# bottom_simp_power.net
KiCad netlist of a schematic drawn in Altium Designer
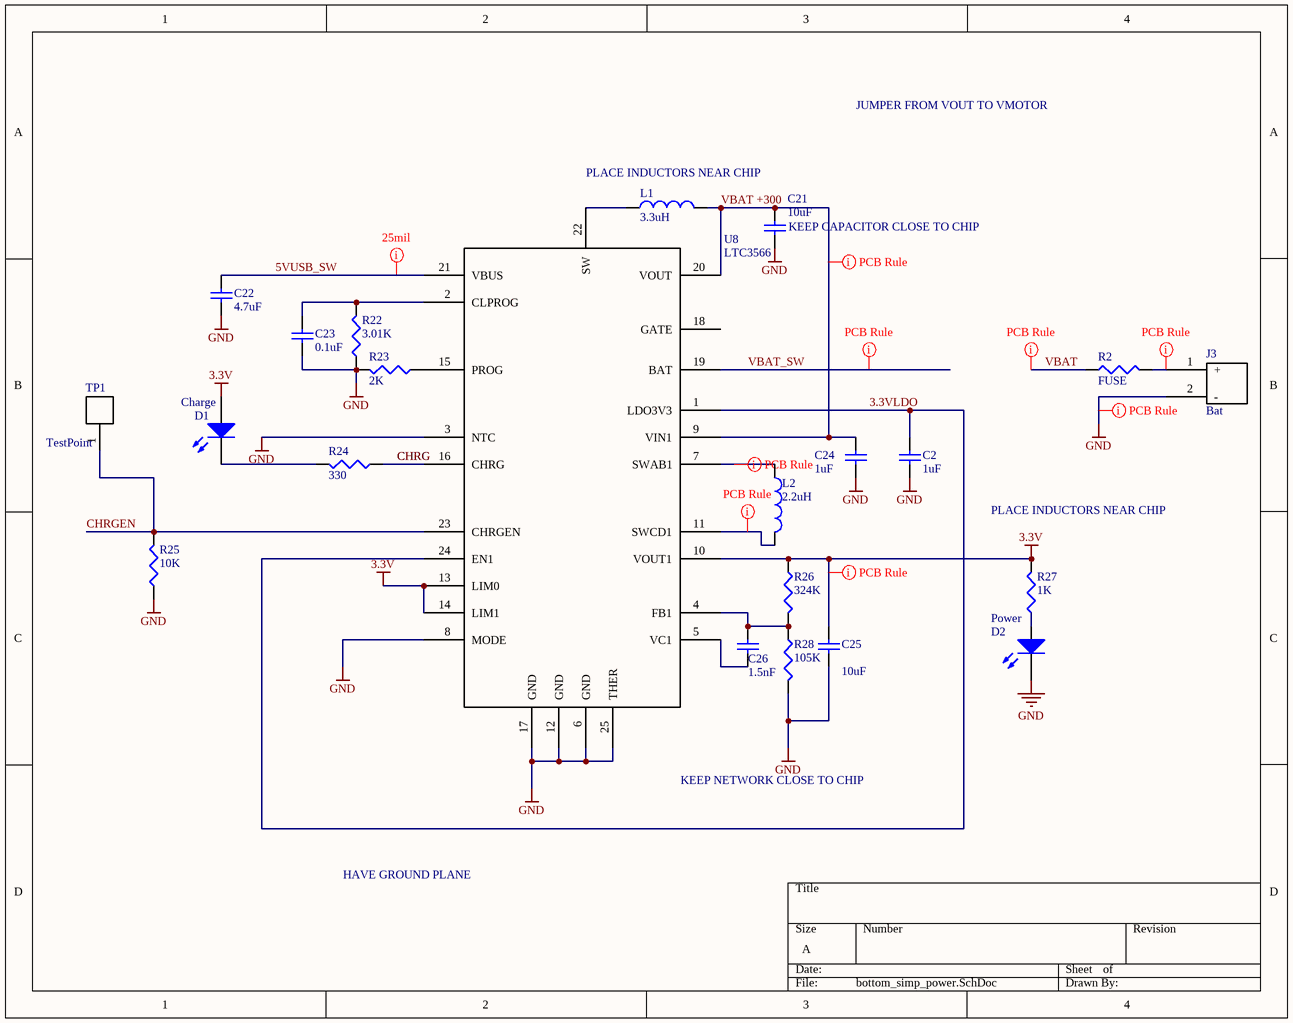
[diagram p0: bottom_simp_power.SchDoc]

(export (version "E")
  (design (tool "Eeschema 10.0.6"))
  (components
    (comp (ref "C2")
      (value "1uF")
      (footprint "CAPC1608L")
      (description "Capacitor")
      (fields (field (name "Comment") "Cap") (field (name "PUBLISHER") "Altium Limited"))
      (libsource (lib "Miscellaneous Devices") (part "Cap"))
    )
    (comp (ref "C21")
      (value "10uF")
      (footprint "CAPC1608L")
      (description "Capacitor")
      (fields (field (name "Comment") "Cap") (field (name "PUBLISHER") "Altium Limited"))
      (libsource (lib "Miscellaneous Devices") (part "Cap"))
    )
    (comp (ref "C22")
      (value "4.7uF")
      (footprint "CAPC1608L")
      (description "Capacitor")
      (fields (field (name "Comment") "Cap") (field (name "PUBLISHER") "Altium Limited"))
      (libsource (lib "Miscellaneous Devices") (part "Cap"))
    )
    (comp (ref "C23")
      (value "0.1uF")
      (footprint "CAPC1005L")
      (description "Capacitor")
      (fields (field (name "Comment") "Cap") (field (name "PUBLISHER") "Altium Limited"))
      (libsource (lib "Miscellaneous Devices") (part "Cap"))
    )
    (comp (ref "C24")
      (value "1uF")
      (footprint "CAPC1608L")
      (description "Capacitor")
      (fields (field (name "Comment") "Cap") (field (name "PUBLISHER") "Altium Limited"))
      (libsource (lib "Miscellaneous Devices") (part "Cap"))
    )
    (comp (ref "C25")
      (value "10uF")
      (footprint "CAPC1608L")
      (description "Capacitor")
      (fields (field (name "Comment") "Cap") (field (name "PUBLISHER") "Altium Limited"))
      (libsource (lib "Miscellaneous Devices") (part "Cap"))
    )
    (comp (ref "C26")
      (value "1.5nF")
      (footprint "CAPC1005L")
      (description "Capacitor")
      (fields (field (name "Comment") "Cap") (field (name "PUBLISHER") "Altium Limited"))
      (libsource (lib "Miscellaneous Devices") (part "Cap"))
    )
    (comp (ref "D1")
      (value "Charge")
      (footprint "INDC2012L")
      (description "Typical RED, GREEN, YELLOW, AMBER GaAs LED")
      (fields (field (name "PUBLISHER") "Altium Limited"))
      (libsource (lib "Miscellaneous Devices") (part "LED2"))
    )
    (comp (ref "D2")
      (value "Power")
      (footprint "INDC2012L")
      (description "Typical RED, GREEN, YELLOW, AMBER GaAs LED")
      (fields (field (name "PUBLISHER") "Altium Limited"))
      (libsource (lib "Miscellaneous Devices") (part "LED2"))
    )
    (comp (ref "J3")
      (value "Bat")
      (footprint "BatteryConnJST")
      (libsource (lib "mrone") (part "BatteryConnJST"))
    )
    (comp (ref "L1") (value "3.3uH") (footprint "Inductor-Power") (libsource (lib "mrone") (part "Inductor")))
    (comp (ref "L2") (value "2.2uH") (footprint "Inductor-Power") (libsource (lib "mrone") (part "Inductor")))
    (comp (ref "R2")
      (value "FUSE")
      (footprint "RESC3225L")
      (description "Resistor")
      (fields (field (name "Comment") "Res3") (field (name "PUBLISHER") "Altium Limited"))
      (libsource (lib "Miscellaneous Devices") (part "Res3"))
    )
    (comp (ref "R22")
      (value "3.01K")
      (footprint "RESC1608L")
      (description "Resistor")
      (fields (field (name "Comment") "Res3") (field (name "PUBLISHER") "Altium Limited"))
      (libsource (lib "Miscellaneous Devices") (part "Res3"))
    )
    (comp (ref "R23")
      (value "2K")
      (footprint "RESC1608L")
      (description "Resistor")
      (fields (field (name "Comment") "Res3") (field (name "PUBLISHER") "Altium Limited"))
      (libsource (lib "Miscellaneous Devices") (part "Res3"))
    )
    (comp (ref "R24")
      (value "330")
      (footprint "RESC1608L")
      (description "Resistor")
      (fields (field (name "Comment") "Res3") (field (name "PUBLISHER") "Altium Limited"))
      (libsource (lib "Miscellaneous Devices") (part "Res3"))
    )
    (comp (ref "R25")
      (value "10K")
      (footprint "RESC1608L")
      (description "Resistor")
      (fields (field (name "Comment") "Res3") (field (name "PUBLISHER") "Altium Limited"))
      (libsource (lib "Miscellaneous Devices") (part "Res3"))
    )
    (comp (ref "R26")
      (value "324K")
      (footprint "RESC1608L")
      (description "Resistor")
      (fields (field (name "Comment") "Res3") (field (name "PUBLISHER") "Altium Limited"))
      (libsource (lib "Miscellaneous Devices") (part "Res3"))
    )
    (comp (ref "R27")
      (value "1K")
      (footprint "RESC1608L")
      (description "Resistor")
      (fields (field (name "Comment") "Res3") (field (name "PUBLISHER") "Altium Limited"))
      (libsource (lib "Miscellaneous Devices") (part "Res3"))
    )
    (comp (ref "R28")
      (value "105K")
      (footprint "RESC1608L")
      (description "Resistor")
      (fields (field (name "Comment") "Res3") (field (name "PUBLISHER") "Altium Limited"))
      (libsource (lib "Miscellaneous Devices") (part "Res3"))
    )
    (comp (ref "TP1")
      (value "TestPoint")
      (footprint "TestPoint")
      (libsource (lib "mrone") (part "TestPoint"))
    )
    (comp (ref "U8")
      (value "LTC3566")
      (footprint "QFN-24")
      (libsource (lib "Schematic Components") (part "LTC3566"))
    )
  )
  (nets
    (net (code "1") (name "/3.3VLDO") (class "Default")
      (node (ref "C2") (pin "1") (pinfunction "1_1") (pintype "passive"))
      (node (ref "U8") (pin "1") (pinfunction "LDO3V3_1") (pintype "passive"))
      (node (ref "U8") (pin "24") (pinfunction "EN1_24") (pintype "passive"))
    )
    (net (code "2") (name "/5VUSB_SW") (class "Default")
      (node (ref "C22") (pin "2") (pinfunction "2_2") (pintype "passive"))
      (node (ref "U8") (pin "21") (pinfunction "VBUS_21") (pintype "passive"))
    )
    (net (code "3") (name "/CHRG") (class "Default")
      (node (ref "R24") (pin "1") (pinfunction "1_1") (pintype "passive"))
      (node (ref "U8") (pin "16") (pinfunction "CHRG_16") (pintype "passive"))
    )
    (net (code "4") (name "/CHRGEN") (class "Default")
      (node (ref "R25") (pin "2") (pinfunction "2_2") (pintype "passive"))
      (node (ref "TP1") (pin "1") (pintype "passive"))
      (node (ref "U8") (pin "23") (pinfunction "CHRGEN_23") (pintype "passive"))
    )
    (net (code "5") (name "/VBAT") (class "Default")
      (node (ref "R2") (pin "1") (pinfunction "1_1") (pintype "passive"))
    )
    (net (code "6") (name "/VBAT +300") (class "Default")
      (node (ref "C21") (pin "2") (pinfunction "2_2") (pintype "passive"))
      (node (ref "C24") (pin "1") (pinfunction "1_1") (pintype "passive"))
      (node (ref "L1") (pin "2") (pinfunction "2_2") (pintype "passive"))
      (node (ref "U8") (pin "20") (pinfunction "VOUT_20") (pintype "passive"))
      (node (ref "U8") (pin "9") (pinfunction "VIN1_9") (pintype "passive"))
    )
    (net (code "7") (name "/VBAT_SW") (class "Default")
      (node (ref "U8") (pin "19") (pinfunction "BAT_19") (pintype "passive"))
    )
    (net (code "8") (name "3.3V") (class "Default")
      (node (ref "C25") (pin "2") (pinfunction "2_2") (pintype "passive"))
      (node (ref "D1") (pin "1") (pinfunction "A_1") (pintype "passive"))
      (node (ref "R26") (pin "1") (pinfunction "1_1") (pintype "passive"))
      (node (ref "R27") (pin "2") (pinfunction "2_2") (pintype "passive"))
      (node (ref "U8") (pin "10") (pinfunction "VOUT1_10") (pintype "passive"))
      (node (ref "U8") (pin "13") (pinfunction "LIM0_13") (pintype "passive"))
      (node (ref "U8") (pin "14") (pinfunction "LIM1_14") (pintype "passive"))
    )
    (net (code "9") (name "GND") (class "Default")
      (node (ref "C2") (pin "2") (pinfunction "2_2") (pintype "passive"))
      (node (ref "C21") (pin "1") (pinfunction "1_1") (pintype "passive"))
      (node (ref "C22") (pin "1") (pinfunction "1_1") (pintype "passive"))
      (node (ref "C23") (pin "1") (pinfunction "1_1") (pintype "passive"))
      (node (ref "C24") (pin "2") (pinfunction "2_2") (pintype "passive"))
      (node (ref "C25") (pin "1") (pinfunction "1_1") (pintype "passive"))
      (node (ref "D2") (pin "2") (pinfunction "K_2") (pintype "passive"))
      (node (ref "J3") (pin "2") (pinfunction "-_2") (pintype "passive"))
      (node (ref "R22") (pin "1") (pinfunction "1_1") (pintype "passive"))
      (node (ref "R23") (pin "2") (pinfunction "2_2") (pintype "passive"))
      (node (ref "R25") (pin "1") (pinfunction "1_1") (pintype "passive"))
      (node (ref "R28") (pin "2") (pinfunction "2_2") (pintype "passive"))
      (node (ref "U8") (pin "12") (pinfunction "GND_12") (pintype "passive"))
      (node (ref "U8") (pin "17") (pinfunction "GND_17") (pintype "passive"))
      (node (ref "U8") (pin "25") (pinfunction "THER_25") (pintype "passive"))
      (node (ref "U8") (pin "3") (pinfunction "NTC_3") (pintype "passive"))
      (node (ref "U8") (pin "6") (pinfunction "GND_6") (pintype "passive"))
      (node (ref "U8") (pin "8") (pinfunction "MODE_8") (pintype "passive"))
    )
    (net (code "10") (name "Net-(D1-K)") (class "Default")
      (node (ref "D1") (pin "2") (pinfunction "K_2") (pintype "passive"))
      (node (ref "R24") (pin "2") (pinfunction "2_2") (pintype "passive"))
    )
    (net (code "11") (name "Net-(D2-A)") (class "Default")
      (node (ref "D2") (pin "1") (pinfunction "A_1") (pintype "passive"))
      (node (ref "R27") (pin "1") (pinfunction "1_1") (pintype "passive"))
    )
    (net (code "12") (name "Net-(J3-+)") (class "Default")
      (node (ref "J3") (pin "1") (pinfunction "+_1") (pintype "passive"))
      (node (ref "R2") (pin "2") (pinfunction "2_2") (pintype "passive"))
    )
    (net (code "13") (name "Net-(U8-CLPROG)") (class "Default")
      (node (ref "C23") (pin "2") (pinfunction "2_2") (pintype "passive"))
      (node (ref "R22") (pin "2") (pinfunction "2_2") (pintype "passive"))
      (node (ref "U8") (pin "2") (pinfunction "CLPROG_2") (pintype "passive"))
    )
    (net (code "14") (name "Net-(U8-FB1)") (class "Default")
      (node (ref "C26") (pin "1") (pinfunction "1_1") (pintype "passive"))
      (node (ref "R26") (pin "2") (pinfunction "2_2") (pintype "passive"))
      (node (ref "R28") (pin "1") (pinfunction "1_1") (pintype "passive"))
      (node (ref "U8") (pin "4") (pinfunction "FB1_4") (pintype "passive"))
    )
    (net (code "15") (name "Net-(U8-PROG)") (class "Default")
      (node (ref "R23") (pin "1") (pinfunction "1_1") (pintype "passive"))
      (node (ref "U8") (pin "15") (pinfunction "PROG_15") (pintype "passive"))
    )
    (net (code "16") (name "Net-(U8-SW)") (class "Default")
      (node (ref "L1") (pin "1") (pinfunction "1_1") (pintype "passive"))
      (node (ref "U8") (pin "22") (pinfunction "SW_22") (pintype "passive"))
    )
    (net (code "17") (name "Net-(U8-SWAB1)") (class "Default")
      (node (ref "L2") (pin "1") (pinfunction "1_1") (pintype "passive"))
      (node (ref "U8") (pin "7") (pinfunction "SWAB1_7") (pintype "passive"))
    )
    (net (code "18") (name "Net-(U8-SWCD1)") (class "Default")
      (node (ref "L2") (pin "2") (pinfunction "2_2") (pintype "passive"))
      (node (ref "U8") (pin "11") (pinfunction "SWCD1_11") (pintype "passive"))
    )
    (net (code "19") (name "Net-(U8-VC1)") (class "Default")
      (node (ref "C26") (pin "2") (pinfunction "2_2") (pintype "passive"))
      (node (ref "U8") (pin "5") (pinfunction "VC1_5") (pintype "passive"))
    )
    (net (code "20") (name "unconnected-(U8-GATE-Pad18)") (class "Default")
      (node (ref "U8") (pin "18") (pinfunction "GATE_18") (pintype "passive"))
    )
  )
)
